# power_core.net
KiCad netlist of a schematic drawn in Altium Designer
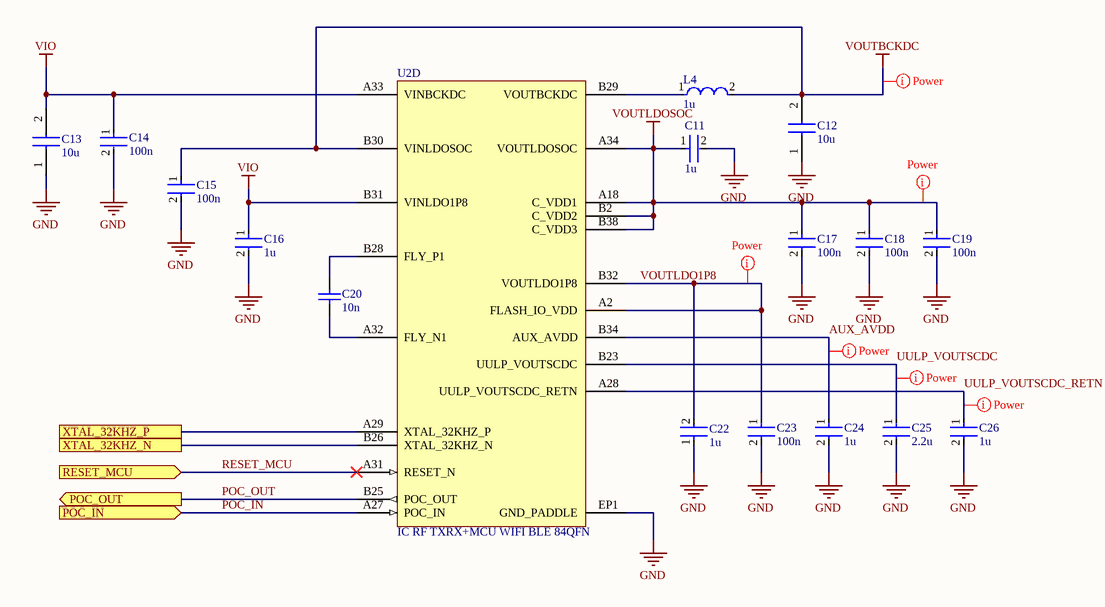
[diagram p0: power_core.SchDoc]

(export (version "E")
  (design (tool "Eeschema 10.0.6"))
  (components
    (comp (ref "C11")
      (value "1u")
      (footprint "FP-GRM155-0_05-MFG")
      (description "Chip Multilayer Ceramic Capacitors for General Purpose, 0402, 1.0uF, X6S, 22%, 10%, 16V")
      (fields (field (name "TOLERANCE") "10%"))
      (libsource (lib "Altium Content Vault") (part "02cd4be3c70576c341d710602a673aa"))
    )
    (comp (ref "C12")
      (value "10u")
      (footprint "SamacSys:CAPC1608X100N")
      (description "Cap Cer 10UF 10V X7R 0603")
      (fields (field (name "MANUFACTURER_PART_NUMBER") "GMC10X7R106K10NT"))
      (libsource (lib "*") (part "GMC10X7R106K10NT"))
    )
    (comp (ref "C13")
      (value "10u")
      (footprint "SamacSys:CAPC1608X100N")
      (description "Cap Cer 10UF 10V X7R 0603")
      (fields (field (name "MANUFACTURER_PART_NUMBER") "GMC10X7R106K10NT"))
      (libsource (lib "*") (part "GMC10X7R106K10NT"))
    )
    (comp (ref "C14")
      (value "100n")
      (footprint "FP-GRT155-0_05-MFG")
      (description "Multi-Layer Ceramic Capacitor 100nF 50V X7R ±10% 0402 Paper T/R")
      (libsource (lib "Altium Content Vault") (part "02cd4be3c70576c341d710602a673aa"))
    )
    (comp (ref "C15")
      (value "100n")
      (footprint "FP-GRT155-0_05-MFG")
      (description "Multi-Layer Ceramic Capacitor 100nF 50V X7R ±10% 0402 Paper T/R")
      (libsource (lib "Altium Content Vault") (part "02cd4be3c70576c341d710602a673aa"))
    )
    (comp (ref "C16")
      (value "1u")
      (footprint "FP-GRM155-0_05-MFG")
      (description "Chip Multilayer Ceramic Capacitors for General Purpose, 0402, 1.0uF, X6S, 22%, 10%, 16V")
      (fields (field (name "TOLERANCE") "10%"))
      (libsource (lib "Altium Content Vault") (part "02cd4be3c70576c341d710602a673aa"))
    )
    (comp (ref "C17")
      (value "100n")
      (footprint "FP-GRT155-0_05-MFG")
      (description "Multi-Layer Ceramic Capacitor 100nF 50V X7R ±10% 0402 Paper T/R")
      (libsource (lib "Altium Content Vault") (part "02cd4be3c70576c341d710602a673aa"))
    )
    (comp (ref "C18")
      (value "100n")
      (footprint "FP-GRT155-0_05-MFG")
      (description "Multi-Layer Ceramic Capacitor 100nF 50V X7R ±10% 0402 Paper T/R")
      (libsource (lib "Altium Content Vault") (part "02cd4be3c70576c341d710602a673aa"))
    )
    (comp (ref "C19")
      (value "100n")
      (footprint "FP-GRT155-0_05-MFG")
      (description "Multi-Layer Ceramic Capacitor 100nF 50V X7R ±10% 0402 Paper T/R")
      (libsource (lib "Altium Content Vault") (part "02cd4be3c70576c341d710602a673aa"))
    )
    (comp (ref "C20")
      (value "10n")
      (footprint "CAPC1005X55X25LL05T10")
      (fields (field (name "MANUFACTURER") "Murata") (field (name "PART NUMBER") "GRM155R71E103KA01D"))
      (libsource (lib "Altium Content Vault") (part "CAP"))
    )
    (comp (ref "C22")
      (value "1u")
      (footprint "FP-GRM155-0_05-MFG")
      (description "Chip Multilayer Ceramic Capacitors for General Purpose, 0402, 1.0uF, X6S, 22%, 10%, 16V")
      (fields (field (name "TOLERANCE") "10%"))
      (libsource (lib "Altium Content Vault") (part "02cd4be3c70576c341d710602a673aa"))
    )
    (comp (ref "C23")
      (value "100n")
      (footprint "FP-GRT155-0_05-MFG")
      (description "Multi-Layer Ceramic Capacitor 100nF 50V X7R ±10% 0402 Paper T/R")
      (libsource (lib "Altium Content Vault") (part "02cd4be3c70576c341d710602a673aa"))
    )
    (comp (ref "C24")
      (value "1u")
      (footprint "FP-GRM155-0_05-MFG")
      (description "Chip Multilayer Ceramic Capacitors for General Purpose, 0402, 1.0uF, X6S, 22%, 10%, 16V")
      (fields (field (name "TOLERANCE") "10%"))
      (libsource (lib "Altium Content Vault") (part "02cd4be3c70576c341d710602a673aa"))
    )
    (comp (ref "C25")
      (value "2.2u")
      (footprint "FP-GRM155-0_2-IPC_C")
      (description "Chip Multilayer Ceramic Capacitors for General Purpose, 0402, 2.2uF, X7S, 22%, 10%, 10V")
      (fields (field (name "TOLERANCE") "10%"))
      (libsource (lib "Altium Content Vault") (part "b4654b650e69147ec39a6b967a45e02"))
    )
    (comp (ref "C26")
      (value "1u")
      (footprint "FP-GRM155-0_05-MFG")
      (description "Chip Multilayer Ceramic Capacitors for General Purpose, 0402, 1.0uF, X6S, 22%, 10%, 16V")
      (fields (field (name "TOLERANCE") "10%"))
      (libsource (lib "Altium Content Vault") (part "02cd4be3c70576c341d710602a673aa"))
    )
    (comp (ref "L4")
      (value "1u")
      (footprint "FP-DFE201210U-IPC_C")
      (description "FIXED IND 1.0UH 2.0A 95MOHM")
      (libsource (lib "Altium Content Vault") (part "725321dda6339637d4d059423bc1c3c"))
    )
    (comp (ref "U2")
      (value "IC RF TXRX+MCU WIFI BLE 84QFN")
      (footprint "SIWG917M110LGTBA")
      (libsource (lib "SiWG917") (part "SIWG917"))
    )
  )
  (nets
    (net (code "1") (name "/AUX_AVDD") (class "Default")
      (node (ref "C24") (pin "1") (pinfunction "1_1") (pintype "passive"))
      (node (ref "U2") (pin "B34") (pinfunction "AUX_AVDD_B34") (pintype "passive"))
    )
    (net (code "2") (name "/POC_IN") (class "Default")
      (node (ref "U2") (pin "A27") (pinfunction "POC_IN_A27") (pintype "input"))
    )
    (net (code "3") (name "/POC_OUT") (class "Default")
      (node (ref "U2") (pin "B25") (pinfunction "POC_OUT_B25") (pintype "output"))
    )
    (net (code "4") (name "/RESET_MCU") (class "Default")
      (node (ref "U2") (pin "A31") (pinfunction "RESET_N_A31") (pintype "input+no_connect"))
    )
    (net (code "5") (name "/UULP_VOUTSCDC") (class "Default")
      (node (ref "C25") (pin "1") (pinfunction "1_1") (pintype "passive"))
      (node (ref "U2") (pin "B23") (pinfunction "UULP_VOUTSCDC_B23") (pintype "passive"))
    )
    (net (code "6") (name "/UULP_VOUTSCDC_RETN") (class "Default")
      (node (ref "C26") (pin "1") (pinfunction "1_1") (pintype "passive"))
      (node (ref "U2") (pin "A28") (pinfunction "UULP_VOUTSCDC_RETN_A28") (pintype "passive"))
    )
    (net (code "7") (name "/VOUTLDO1P8") (class "Default")
      (node (ref "C22") (pin "2") (pinfunction "2_2") (pintype "passive"))
      (node (ref "C23") (pin "1") (pinfunction "1_1") (pintype "passive"))
      (node (ref "U2") (pin "A2") (pinfunction "FLASH_IO_VDD_A2") (pintype "power_in"))
      (node (ref "U2") (pin "B32") (pinfunction "VOUTLDO1P8_B32") (pintype "power_in"))
    )
    (net (code "8") (name "/XTAL_32KHZ_N") (class "Default")
      (node (ref "U2") (pin "B26") (pinfunction "XTAL_32KHZ_N_B26") (pintype "passive"))
    )
    (net (code "9") (name "/XTAL_32KHZ_P") (class "Default")
      (node (ref "U2") (pin "A29") (pinfunction "XTAL_32KHZ_P_A29") (pintype "passive"))
    )
    (net (code "10") (name "GND") (class "Default")
      (node (ref "C11") (pin "2") (pinfunction "2_2") (pintype "passive"))
      (node (ref "C12") (pin "1") (pinfunction "1_1") (pintype "passive"))
      (node (ref "C13") (pin "1") (pinfunction "1_1") (pintype "passive"))
      (node (ref "C14") (pin "2") (pinfunction "2_2") (pintype "passive"))
      (node (ref "C15") (pin "2") (pinfunction "2_2") (pintype "passive"))
      (node (ref "C16") (pin "2") (pinfunction "2_2") (pintype "passive"))
      (node (ref "C17") (pin "2") (pinfunction "2_2") (pintype "passive"))
      (node (ref "C18") (pin "2") (pinfunction "2_2") (pintype "passive"))
      (node (ref "C19") (pin "2") (pinfunction "2_2") (pintype "passive"))
      (node (ref "C22") (pin "1") (pinfunction "1_1") (pintype "passive"))
      (node (ref "C23") (pin "2") (pinfunction "2_2") (pintype "passive"))
      (node (ref "C24") (pin "2") (pinfunction "2_2") (pintype "passive"))
      (node (ref "C25") (pin "2") (pinfunction "2_2") (pintype "passive"))
      (node (ref "C26") (pin "2") (pinfunction "2_2") (pintype "passive"))
      (node (ref "U2") (pin "EP1") (pinfunction "GND_PADDLE_EP1") (pintype "power_in"))
    )
    (net (code "11") (name "Net-(U2D-FLY_N1)") (class "Default")
      (node (ref "C20") (pin "2") (pinfunction "2_2") (pintype "passive"))
      (node (ref "U2") (pin "A32") (pinfunction "FLY_N1_A32") (pintype "passive"))
    )
    (net (code "12") (name "Net-(U2D-FLY_P1)") (class "Default")
      (node (ref "C20") (pin "1") (pinfunction "1_1") (pintype "passive"))
      (node (ref "U2") (pin "B28") (pinfunction "FLY_P1_B28") (pintype "passive"))
    )
    (net (code "13") (name "Net-(U2D-VOUTBCKDC)") (class "Default")
      (node (ref "L4") (pin "1") (pinfunction "1_1") (pintype "passive"))
      (node (ref "U2") (pin "B29") (pinfunction "VOUTBCKDC_B29") (pintype "power_in"))
    )
    (net (code "14") (name "VIO") (class "Default")
      (node (ref "C13") (pin "2") (pinfunction "2_2") (pintype "passive"))
      (node (ref "C14") (pin "1") (pinfunction "1_1") (pintype "passive"))
      (node (ref "C16") (pin "1") (pinfunction "1_1") (pintype "passive"))
      (node (ref "U2") (pin "A33") (pinfunction "VINBCKDC_A33") (pintype "power_in"))
      (node (ref "U2") (pin "B31") (pinfunction "VINLDO1P8_B31") (pintype "power_in"))
    )
    (net (code "15") (name "VOUTBCKDC") (class "Default")
      (node (ref "C12") (pin "2") (pinfunction "2_2") (pintype "passive"))
      (node (ref "C15") (pin "1") (pinfunction "1_1") (pintype "passive"))
      (node (ref "L4") (pin "2") (pinfunction "2_2") (pintype "passive"))
      (node (ref "U2") (pin "B30") (pinfunction "VINLDOSOC_B30") (pintype "power_in"))
    )
    (net (code "16") (name "VOUTLDOSOC") (class "Default")
      (node (ref "C11") (pin "1") (pinfunction "1_1") (pintype "passive"))
      (node (ref "C17") (pin "1") (pinfunction "1_1") (pintype "passive"))
      (node (ref "C18") (pin "1") (pinfunction "1_1") (pintype "passive"))
      (node (ref "C19") (pin "1") (pinfunction "1_1") (pintype "passive"))
      (node (ref "U2") (pin "A18") (pinfunction "C_VDD1_A18") (pintype "power_in"))
      (node (ref "U2") (pin "A34") (pinfunction "VOUTLDOSOC_A34") (pintype "power_in"))
      (node (ref "U2") (pin "B2") (pinfunction "C_VDD2_B2") (pintype "power_in"))
      (node (ref "U2") (pin "B38") (pinfunction "C_VDD3_B38") (pintype "power_in"))
    )
  )
)
